# MCU_144_POWER_Clone.net
KiCad netlist of a schematic drawn in Altium Designer
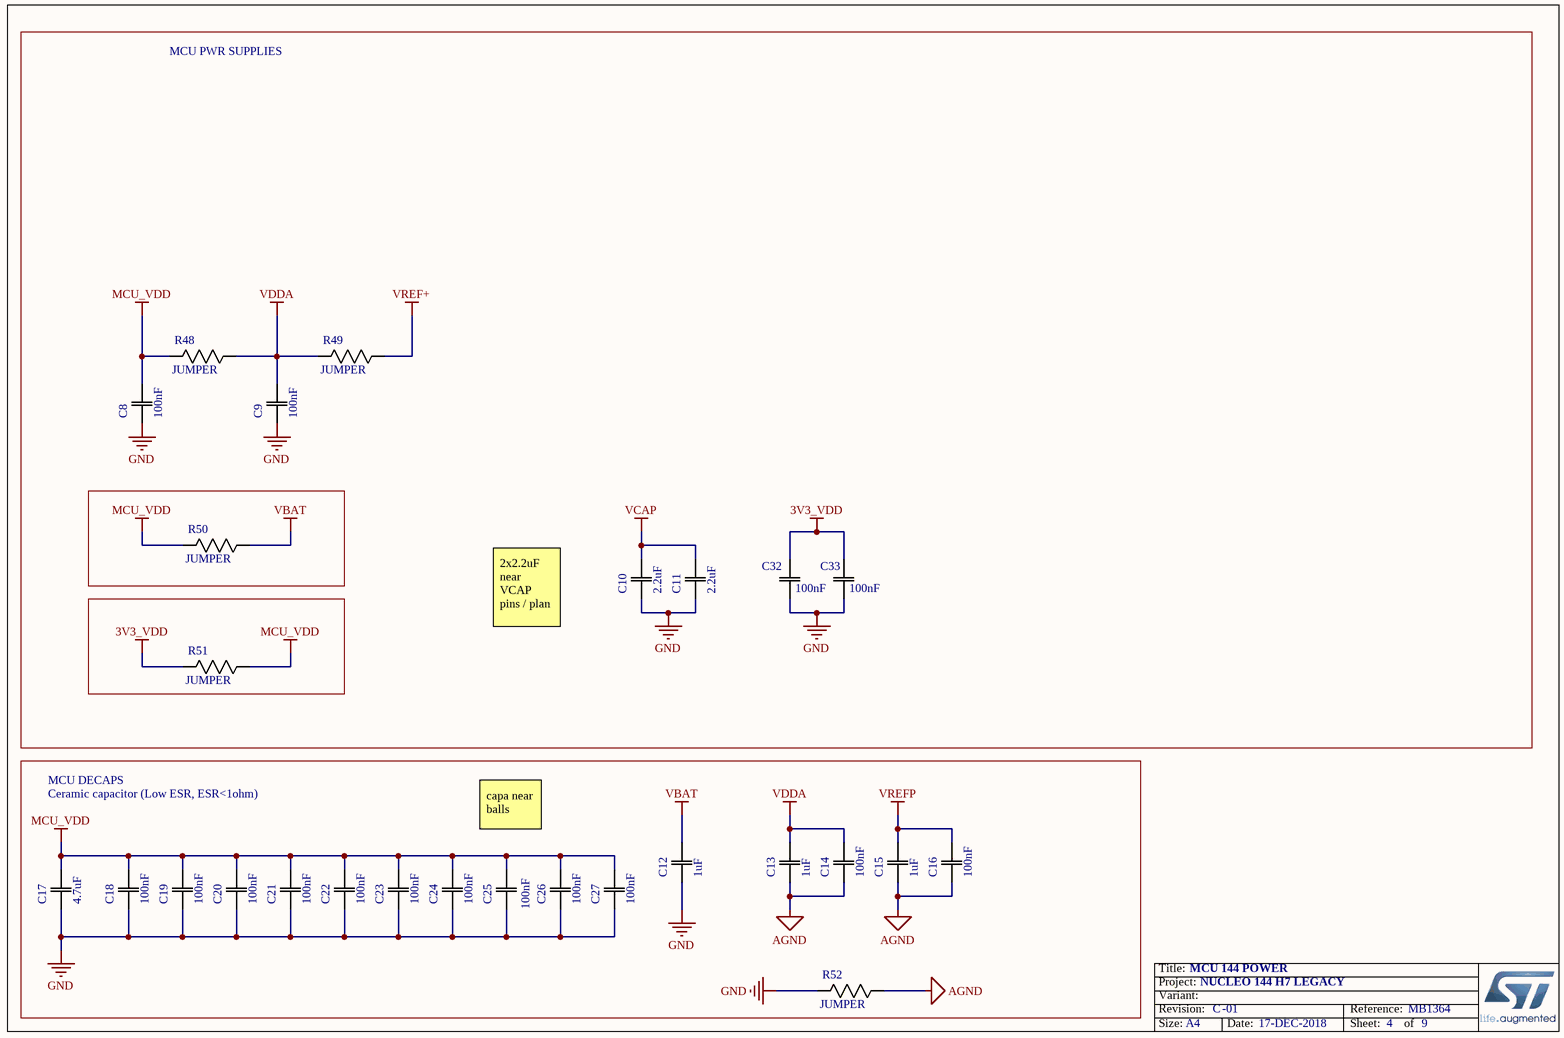
[diagram p0: MCU_144_POWER_Clone.SchDoc]

(export (version "E")
  (design (tool "Eeschema 10.0.6"))
  (components
    (comp (ref "C8")
      (value "100nF")
      (footprint "0805")
      (description "CAP CER 0.1UF 50V X7R 0805")
      (fields (field (name "MP") "CC0805KRX7R9BB104") (field (name "MF") "Yageo"))
      (libsource (lib "AltiumLibraries") (part "CAP 100nF 0805"))
    )
    (comp (ref "C9")
      (value "100nF")
      (footprint "0805")
      (description "CAP CER 0.1UF 50V X7R 0805")
      (fields (field (name "MP") "CC0805KRX7R9BB104") (field (name "MF") "Yageo"))
      (libsource (lib "AltiumLibraries") (part "CAP 100nF 0805"))
    )
    (comp (ref "C10")
      (value "2.2uF")
      (footprint "0805")
      (description "CAP CER 1UF 50V X7R 0805")
      (fields (field (name "MP") "C0805C225K4RACTU") (field (name "MF") "KEMET"))
      (libsource (lib "AltiumLibraries") (part "CAP 2.2uF 0805"))
    )
    (comp (ref "C11")
      (value "2.2uF")
      (footprint "0805")
      (description "CAP CER 1UF 50V X7R 0805")
      (fields (field (name "MP") "C0805C225K4RACTU") (field (name "MF") "KEMET"))
      (libsource (lib "AltiumLibraries") (part "CAP 2.2uF 0805"))
    )
    (comp (ref "C12")
      (value "1uF")
      (footprint "0805")
      (description "CAP CER 1UF 50V X7R 0805")
      (fields (field (name "MP") "CL21B105KBFNNNE") (field (name "MF") "Samsung Electro-Mechanics"))
      (libsource (lib "AltiumLibraries") (part "CAP 1uF 0805"))
    )
    (comp (ref "C13")
      (value "1uF")
      (footprint "0805")
      (description "CAP CER 1UF 50V X7R 0805")
      (fields (field (name "MP") "CL21B105KBFNNNE") (field (name "MF") "Samsung Electro-Mechanics"))
      (libsource (lib "AltiumLibraries") (part "CAP 1uF 0805"))
    )
    (comp (ref "C14")
      (value "100nF")
      (footprint "0805")
      (description "CAP CER 0.1UF 50V X7R 0805")
      (fields (field (name "MP") "CC0805KRX7R9BB104") (field (name "MF") "Yageo"))
      (libsource (lib "AltiumLibraries") (part "CAP 100nF 0805"))
    )
    (comp (ref "C15")
      (value "1uF")
      (footprint "0805")
      (description "CAP CER 1UF 50V X7R 0805")
      (fields (field (name "MP") "CL21B105KBFNNNE") (field (name "MF") "Samsung Electro-Mechanics"))
      (libsource (lib "AltiumLibraries") (part "CAP 1uF 0805"))
    )
    (comp (ref "C16")
      (value "100nF")
      (footprint "0805")
      (description "CAP CER 0.1UF 50V X7R 0805")
      (fields (field (name "MP") "CC0805KRX7R9BB104") (field (name "MF") "Yageo"))
      (libsource (lib "AltiumLibraries") (part "CAP 100nF 0805"))
    )
    (comp (ref "C17")
      (value "4.7uF")
      (footprint "0805")
      (description "CAP CER 4.7UF 25V X5R 0805")
      (fields (field (name "MP") "CL21B475KOFNNNE") (field (name "MF") "Samsung Electro-Mechanics"))
      (libsource (lib "AltiumLibraries") (part "CAP 4.7uF 0805"))
    )
    (comp (ref "C18")
      (value "100nF")
      (footprint "0805")
      (description "CAP CER 0.1UF 50V X7R 0805")
      (fields (field (name "MP") "CC0805KRX7R9BB104") (field (name "MF") "Yageo"))
      (libsource (lib "AltiumLibraries") (part "CAP 100nF 0805"))
    )
    (comp (ref "C19")
      (value "100nF")
      (footprint "0805")
      (description "CAP CER 0.1UF 50V X7R 0805")
      (fields (field (name "MP") "CC0805KRX7R9BB104") (field (name "MF") "Yageo"))
      (libsource (lib "AltiumLibraries") (part "CAP 100nF 0805"))
    )
    (comp (ref "C20")
      (value "100nF")
      (footprint "0805")
      (description "CAP CER 0.1UF 50V X7R 0805")
      (fields (field (name "MP") "CC0805KRX7R9BB104") (field (name "MF") "Yageo"))
      (libsource (lib "AltiumLibraries") (part "CAP 100nF 0805"))
    )
    (comp (ref "C21")
      (value "100nF")
      (footprint "0805")
      (description "CAP CER 0.1UF 50V X7R 0805")
      (fields (field (name "MP") "CC0805KRX7R9BB104") (field (name "MF") "Yageo"))
      (libsource (lib "AltiumLibraries") (part "CAP 100nF 0805"))
    )
    (comp (ref "C22")
      (value "100nF")
      (footprint "0805")
      (description "CAP CER 0.1UF 50V X7R 0805")
      (fields (field (name "MP") "CC0805KRX7R9BB104") (field (name "MF") "Yageo"))
      (libsource (lib "AltiumLibraries") (part "CAP 100nF 0805"))
    )
    (comp (ref "C23")
      (value "100nF")
      (footprint "0805")
      (description "CAP CER 0.1UF 50V X7R 0805")
      (fields (field (name "MP") "CC0805KRX7R9BB104") (field (name "MF") "Yageo"))
      (libsource (lib "AltiumLibraries") (part "CAP 100nF 0805"))
    )
    (comp (ref "C24")
      (value "100nF")
      (footprint "0805")
      (description "CAP CER 0.1UF 50V X7R 0805")
      (fields (field (name "MP") "CC0805KRX7R9BB104") (field (name "MF") "Yageo"))
      (libsource (lib "AltiumLibraries") (part "CAP 100nF 0805"))
    )
    (comp (ref "C25")
      (value "100nF")
      (footprint "0805")
      (description "CAP CER 0.1UF 50V X7R 0805")
      (fields (field (name "MP") "CC0805KRX7R9BB104") (field (name "MF") "Yageo"))
      (libsource (lib "AltiumLibraries") (part "CAP 100nF 0805"))
    )
    (comp (ref "C26")
      (value "100nF")
      (footprint "0805")
      (description "CAP CER 0.1UF 50V X7R 0805")
      (fields (field (name "MP") "CC0805KRX7R9BB104") (field (name "MF") "Yageo"))
      (libsource (lib "AltiumLibraries") (part "CAP 100nF 0805"))
    )
    (comp (ref "C27")
      (value "100nF")
      (footprint "0805")
      (description "CAP CER 0.1UF 50V X7R 0805")
      (fields (field (name "MP") "CC0805KRX7R9BB104") (field (name "MF") "Yageo"))
      (libsource (lib "AltiumLibraries") (part "CAP 100nF 0805"))
    )
    (comp (ref "C32")
      (value "100nF")
      (footprint "0805")
      (description "CAP CER 0.1UF 50V X7R 0805")
      (fields (field (name "MP") "CC0805KRX7R9BB104") (field (name "MF") "Yageo"))
      (libsource (lib "AltiumLibraries") (part "CAP 100nF 0805"))
    )
    (comp (ref "C33")
      (value "100nF")
      (footprint "0805")
      (description "CAP CER 0.1UF 50V X7R 0805")
      (fields (field (name "MP") "CC0805KRX7R9BB104") (field (name "MF") "Yageo"))
      (libsource (lib "AltiumLibraries") (part "CAP 100nF 0805"))
    )
    (comp (ref "R48")
      (value "JUMPER")
      (footprint "0805")
      (description "RES SMD 0 OHM JUMPER 1/8W 0805")
      (fields (field (name "MP") "RC0805JR-070RL") (field (name "MF") "Yageo"))
      (libsource (lib "") (part "RES 0 0805_1"))
    )
    (comp (ref "R49")
      (value "JUMPER")
      (footprint "0805")
      (description "RES SMD 0 OHM JUMPER 1/8W 0805")
      (fields (field (name "MP") "RC0805JR-070RL") (field (name "MF") "Yageo"))
      (libsource (lib "") (part "RES 0 0805_1"))
    )
    (comp (ref "R50")
      (value "JUMPER")
      (footprint "0805")
      (description "RES SMD 0 OHM JUMPER 1/8W 0805")
      (fields (field (name "MP") "RC0805JR-070RL") (field (name "MF") "Yageo"))
      (libsource (lib "") (part "RES 0 0805_1"))
    )
    (comp (ref "R51")
      (value "JUMPER")
      (footprint "0805")
      (description "RES SMD 0 OHM JUMPER 1/8W 0805")
      (fields (field (name "MP") "RC0805JR-070RL") (field (name "MF") "Yageo"))
      (libsource (lib "") (part "RES 0 0805_1"))
    )
    (comp (ref "R52")
      (value "JUMPER")
      (footprint "0805")
      (description "RES SMD 0 OHM JUMPER 1/8W 0805")
      (fields (field (name "MP") "RC0805JR-070RL") (field (name "MF") "Yageo"))
      (libsource (lib "AltiumLibraries") (part "RES 0 0805"))
    )
  )
  (nets
    (net (code "1") (name "3V3_VDD") (class "Default")
      (node (ref "C32") (pin "2") (pinfunction "C2_2") (pintype "passive"))
      (node (ref "C33") (pin "2") (pinfunction "C2_2") (pintype "passive"))
      (node (ref "R51") (pin "2") (pinfunction "R2_2") (pintype "passive"))
    )
    (net (code "2") (name "AGND") (class "Default")
      (node (ref "C13") (pin "1") (pinfunction "C1_1") (pintype "passive"))
      (node (ref "C14") (pin "1") (pinfunction "C1_1") (pintype "passive"))
      (node (ref "C15") (pin "1") (pinfunction "C1_1") (pintype "passive"))
      (node (ref "C16") (pin "1") (pinfunction "C1_1") (pintype "passive"))
      (node (ref "R52") (pin "1") (pinfunction "R1_1") (pintype "passive"))
    )
    (net (code "3") (name "GND") (class "Default")
      (node (ref "C10") (pin "1") (pinfunction "C1_1") (pintype "passive"))
      (node (ref "C11") (pin "1") (pinfunction "C1_1") (pintype "passive"))
      (node (ref "C12") (pin "1") (pinfunction "C1_1") (pintype "passive"))
      (node (ref "C17") (pin "1") (pinfunction "C1_1") (pintype "passive"))
      (node (ref "C18") (pin "1") (pinfunction "C1_1") (pintype "passive"))
      (node (ref "C19") (pin "1") (pinfunction "C1_1") (pintype "passive"))
      (node (ref "C20") (pin "1") (pinfunction "C1_1") (pintype "passive"))
      (node (ref "C21") (pin "1") (pinfunction "C1_1") (pintype "passive"))
      (node (ref "C22") (pin "1") (pinfunction "C1_1") (pintype "passive"))
      (node (ref "C23") (pin "1") (pinfunction "C1_1") (pintype "passive"))
      (node (ref "C24") (pin "1") (pinfunction "C1_1") (pintype "passive"))
      (node (ref "C25") (pin "1") (pinfunction "C1_1") (pintype "passive"))
      (node (ref "C26") (pin "1") (pinfunction "C1_1") (pintype "passive"))
      (node (ref "C27") (pin "1") (pinfunction "C1_1") (pintype "passive"))
      (node (ref "C32") (pin "1") (pinfunction "C1_1") (pintype "passive"))
      (node (ref "C33") (pin "1") (pinfunction "C1_1") (pintype "passive"))
      (node (ref "C8") (pin "1") (pinfunction "C1_1") (pintype "passive"))
      (node (ref "C9") (pin "1") (pinfunction "C1_1") (pintype "passive"))
      (node (ref "R52") (pin "2") (pinfunction "R2_2") (pintype "passive"))
    )
    (net (code "4") (name "MCU_VDD") (class "Default")
      (node (ref "C17") (pin "2") (pinfunction "C2_2") (pintype "passive"))
      (node (ref "C18") (pin "2") (pinfunction "C2_2") (pintype "passive"))
      (node (ref "C19") (pin "2") (pinfunction "C2_2") (pintype "passive"))
      (node (ref "C20") (pin "2") (pinfunction "C2_2") (pintype "passive"))
      (node (ref "C21") (pin "2") (pinfunction "C2_2") (pintype "passive"))
      (node (ref "C22") (pin "2") (pinfunction "C2_2") (pintype "passive"))
      (node (ref "C23") (pin "2") (pinfunction "C2_2") (pintype "passive"))
      (node (ref "C24") (pin "2") (pinfunction "C2_2") (pintype "passive"))
      (node (ref "C25") (pin "2") (pinfunction "C2_2") (pintype "passive"))
      (node (ref "C26") (pin "2") (pinfunction "C2_2") (pintype "passive"))
      (node (ref "C27") (pin "2") (pinfunction "C2_2") (pintype "passive"))
      (node (ref "C8") (pin "2") (pinfunction "C2_2") (pintype "passive"))
      (node (ref "R48") (pin "2") (pinfunction "R2_2") (pintype "passive"))
      (node (ref "R50") (pin "2") (pinfunction "R2_2") (pintype "passive"))
      (node (ref "R51") (pin "1") (pinfunction "R1_1") (pintype "passive"))
    )
    (net (code "5") (name "VBAT") (class "Default")
      (node (ref "C12") (pin "2") (pinfunction "C2_2") (pintype "passive"))
      (node (ref "R50") (pin "1") (pinfunction "R1_1") (pintype "passive"))
    )
    (net (code "6") (name "VCAP") (class "Default")
      (node (ref "C10") (pin "2") (pinfunction "C2_2") (pintype "passive"))
      (node (ref "C11") (pin "2") (pinfunction "C2_2") (pintype "passive"))
    )
    (net (code "7") (name "VDDA") (class "Default")
      (node (ref "C13") (pin "2") (pinfunction "C2_2") (pintype "passive"))
      (node (ref "C14") (pin "2") (pinfunction "C2_2") (pintype "passive"))
      (node (ref "C9") (pin "2") (pinfunction "C2_2") (pintype "passive"))
      (node (ref "R48") (pin "1") (pinfunction "R1_1") (pintype "passive"))
      (node (ref "R49") (pin "2") (pinfunction "R2_2") (pintype "passive"))
    )
    (net (code "8") (name "VREF+") (class "Default")
      (node (ref "R49") (pin "1") (pinfunction "R1_1") (pintype "passive"))
    )
    (net (code "9") (name "VREFP") (class "Default")
      (node (ref "C15") (pin "2") (pinfunction "C2_2") (pintype "passive"))
      (node (ref "C16") (pin "2") (pinfunction "C2_2") (pintype "passive"))
    )
  )
)
